# Daughterboard.net
KiCad netlist of a schematic drawn in EAGLE
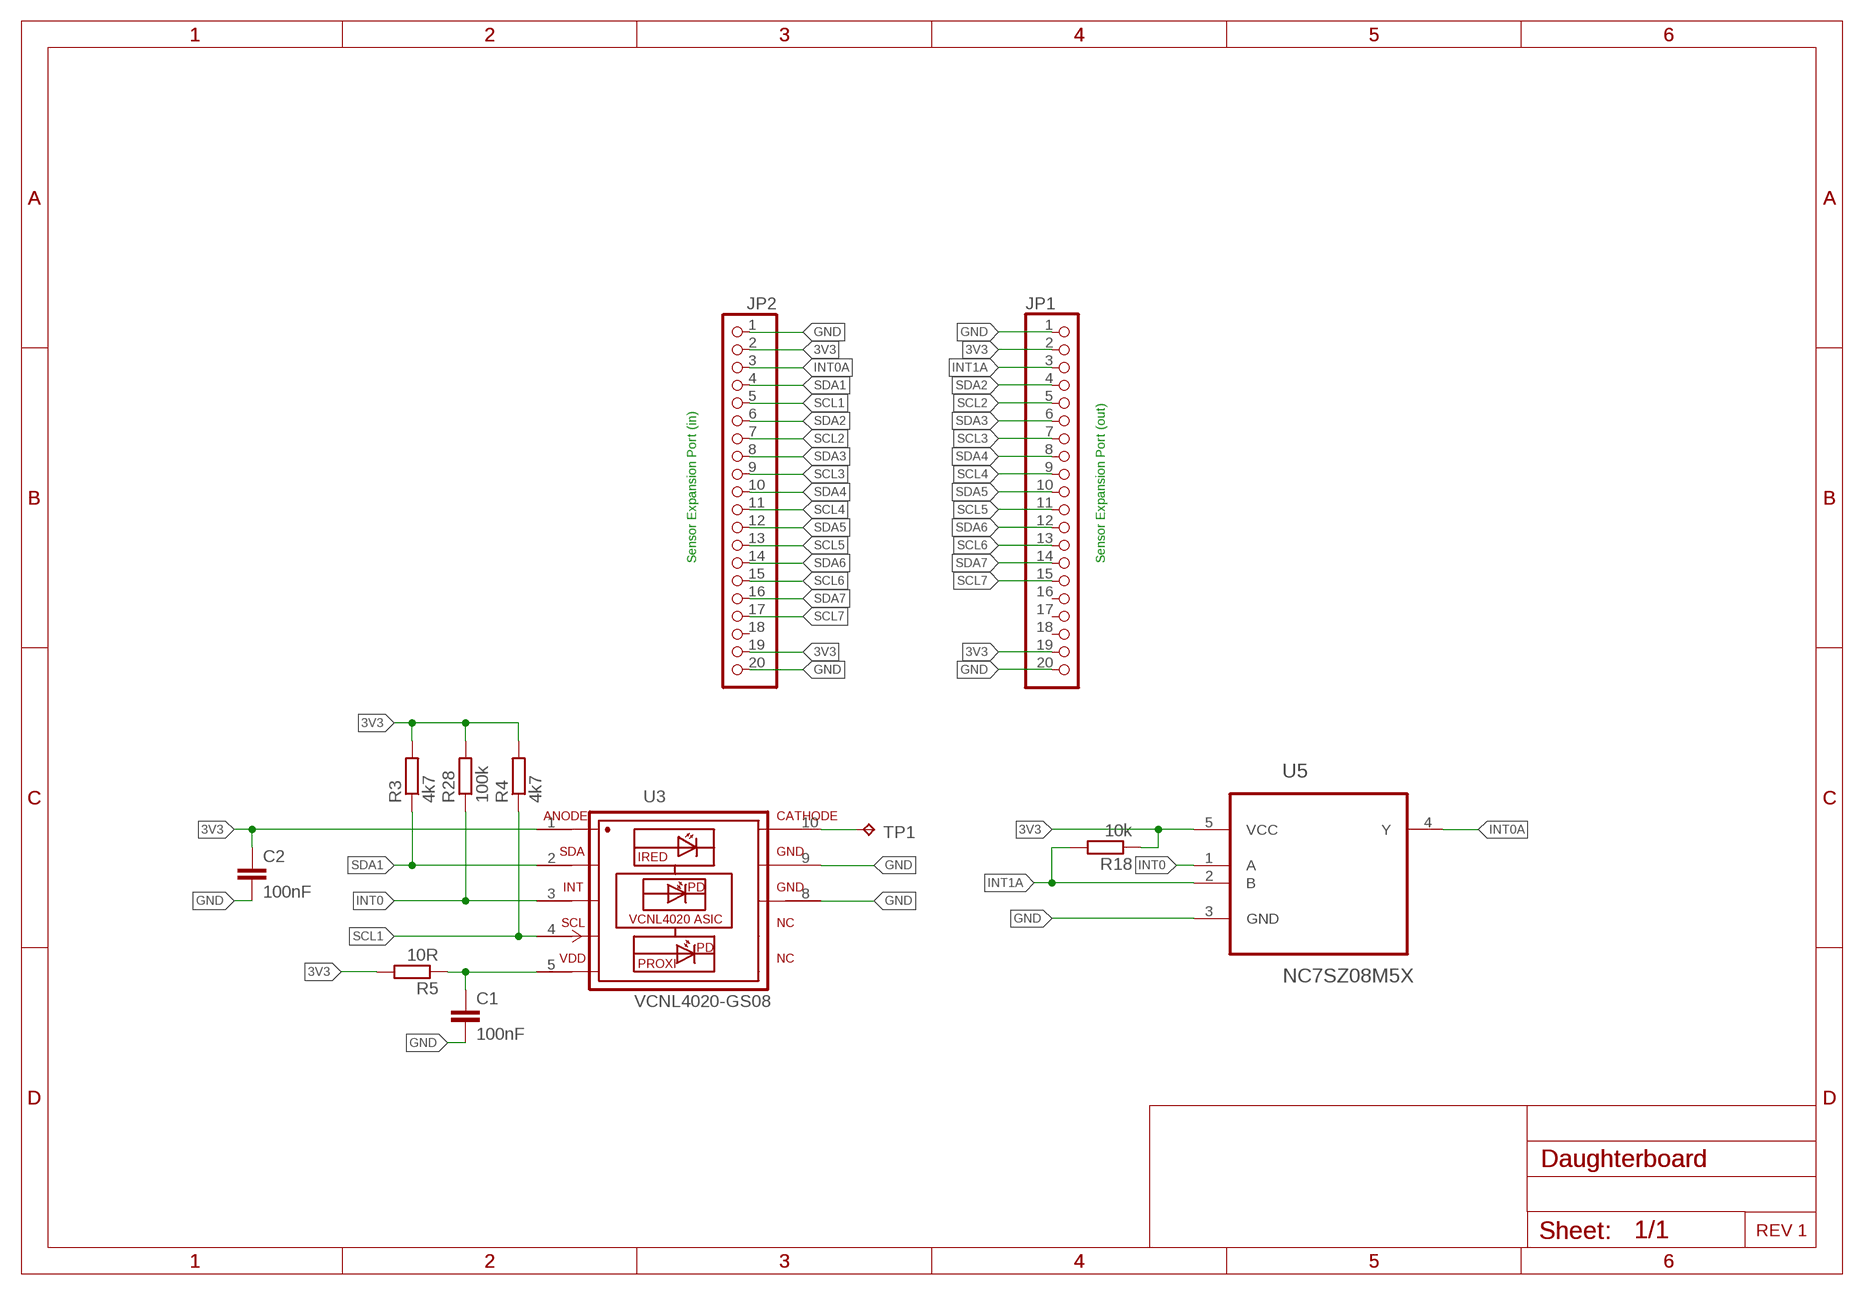
[diagram p0: schematic, sheet 1]

(export (version "E")
  (design (tool "Eeschema 10.0.6"))
  (components
    (comp (ref "C1")
      (value "100nF")
      (footprint "eagle-import:C0603")
      (libsource (lib "eagle-import") (part "C-EUC0603"))
    )
    (comp (ref "C2")
      (value "100nF")
      (footprint "eagle-import:C0603")
      (libsource (lib "eagle-import") (part "C-EUC0603"))
    )
    (comp (ref "JP1")
      (value "PINHD-1X20/90")
      (footprint "eagle-import:1X20_90")
      (libsource (lib "eagle-import") (part "PINHD-1X20/90"))
    )
    (comp (ref "JP2")
      (value "PINHD-1X20/90")
      (footprint "eagle-import:1X20_90")
      (libsource (lib "eagle-import") (part "PINHD-1X20/90"))
    )
    (comp (ref "R3")
      (value "4k7")
      (footprint "eagle-import:R0603")
      (libsource (lib "eagle-import") (part "R-EU_R0603"))
    )
    (comp (ref "R4")
      (value "4k7")
      (footprint "eagle-import:R0603")
      (libsource (lib "eagle-import") (part "R-EU_R0603"))
    )
    (comp (ref "R5")
      (value "10R")
      (footprint "eagle-import:R0603")
      (libsource (lib "eagle-import") (part "R-EU_R0603"))
    )
    (comp (ref "R18")
      (value "10k")
      (footprint "eagle-import:R0603")
      (libsource (lib "eagle-import") (part "R-EU_R0603"))
    )
    (comp (ref "R28")
      (value "100k")
      (footprint "eagle-import:R0603")
      (libsource (lib "eagle-import") (part "R-EU_R0603"))
    )
    (comp (ref "TP1")
      (value "TPB1,27")
      (footprint "eagle-import:B1,27")
      (libsource (lib "eagle-import") (part "TPB1,27"))
    )
    (comp (ref "U3")
      (value "VCNL4020-GS08")
      (footprint "eagle-import:PHODET_VCNL4020")
      (fields (field (name "MF") "Vishay Semiconductor"))
      (libsource (lib "eagle-import") (part "VCNL4020-GS08"))
    )
    (comp (ref "U5")
      (value "NC7SZ08M5X")
      (footprint "eagle-import:SOT95P280X145-5N")
      (fields
        (field (name "DIGI-KEY_PART_NUMBER") "NC7SZ08M5XCT-ND")
        (field (name "MF") "ON Semiconductor")
        (field (name "DIGI-KEY_PART_NUMBER_1") "NC7SZ08M5XCT-ND")
        (field (name "DIGI-KEY_PURCHASE_URL") "https://www.digikey.com/product-detail/en/on-semiconductor/NC7SZ08M5X/NC7SZ08M5XCT-ND/673390?utm_source=snapeda&utm_medium=aggregator&utm_campaign=symbol")
        (field (name "MP") "NC7SZ08M5X")
        (field (name "PACKAGE") "SOT-23 Texas Instruments")
      )
      (libsource (lib "eagle-import") (part "NC7SZ08M5X"))
    )
  )
  (nets
    (net (code "1") (name "3V3") (class "Default")
      (node (ref "C2") (pin "1") (pinfunction "1_1") (pintype "passive"))
      (node (ref "JP1") (pin "19") (pinfunction "19_19") (pintype "passive"))
      (node (ref "JP1") (pin "2") (pinfunction "2_2") (pintype "passive"))
      (node (ref "JP2") (pin "19") (pinfunction "19_19") (pintype "passive"))
      (node (ref "JP2") (pin "2") (pinfunction "2_2") (pintype "passive"))
      (node (ref "R18") (pin "1") (pinfunction "1_1") (pintype "passive"))
      (node (ref "R28") (pin "2") (pinfunction "2_2") (pintype "passive"))
      (node (ref "R3") (pin "2") (pinfunction "2_2") (pintype "passive"))
      (node (ref "R4") (pin "2") (pinfunction "2_2") (pintype "passive"))
      (node (ref "R5") (pin "2") (pinfunction "2_2") (pintype "passive"))
      (node (ref "U3") (pin "1") (pinfunction "IR-ANODE_1") (pintype "passive"))
      (node (ref "U5") (pin "5") (pinfunction "VCC_5") (pintype "power_in"))
    )
    (net (code "2") (name "GND") (class "Default")
      (node (ref "C1") (pin "2") (pinfunction "2_2") (pintype "passive"))
      (node (ref "C2") (pin "2") (pinfunction "2_2") (pintype "passive"))
      (node (ref "JP1") (pin "1") (pinfunction "1_1") (pintype "passive"))
      (node (ref "JP1") (pin "20") (pinfunction "20_20") (pintype "passive"))
      (node (ref "JP2") (pin "1") (pinfunction "1_1") (pintype "passive"))
      (node (ref "JP2") (pin "20") (pinfunction "20_20") (pintype "passive"))
      (node (ref "U3") (pin "8") (pinfunction "GND2_8") (pintype "power_in"))
      (node (ref "U3") (pin "9") (pinfunction "GND_9") (pintype "power_in"))
      (node (ref "U5") (pin "3") (pinfunction "GND_3") (pintype "passive"))
    )
    (net (code "3") (name "INT0") (class "Default")
      (node (ref "R28") (pin "1") (pinfunction "1_1") (pintype "passive"))
      (node (ref "U3") (pin "3") (pinfunction "INT_3") (pintype "output"))
      (node (ref "U5") (pin "1") (pinfunction "A_1") (pintype "input"))
    )
    (net (code "4") (name "INT0A") (class "Default")
      (node (ref "JP2") (pin "3") (pinfunction "3_3") (pintype "passive"))
      (node (ref "U5") (pin "4") (pinfunction "Y_4") (pintype "output"))
    )
    (net (code "5") (name "INT1A") (class "Default")
      (node (ref "JP1") (pin "3") (pinfunction "3_3") (pintype "passive"))
      (node (ref "R18") (pin "2") (pinfunction "2_2") (pintype "passive"))
      (node (ref "U5") (pin "2") (pinfunction "B_2") (pintype "input"))
    )
    (net (code "6") (name "Net-(U3-IR-CATHODE)") (class "Default")
      (node (ref "TP1") (pin "TP") (pinfunction "TP_TP") (pintype "input"))
      (node (ref "U3") (pin "10") (pinfunction "IR-CATHODE_10") (pintype "passive"))
    )
    (net (code "7") (name "Net-(U3-VDD)") (class "Default")
      (node (ref "C1") (pin "1") (pinfunction "1_1") (pintype "passive"))
      (node (ref "R5") (pin "1") (pinfunction "1_1") (pintype "passive"))
      (node (ref "U3") (pin "5") (pinfunction "VDD_5") (pintype "power_in"))
    )
    (net (code "8") (name "SCL1") (class "Default")
      (node (ref "JP2") (pin "5") (pinfunction "5_5") (pintype "passive"))
      (node (ref "R4") (pin "1") (pinfunction "1_1") (pintype "passive"))
      (node (ref "U3") (pin "4") (pinfunction "SCL_4") (pintype "input"))
    )
    (net (code "9") (name "SCL2") (class "Default")
      (node (ref "JP1") (pin "5") (pinfunction "5_5") (pintype "passive"))
      (node (ref "JP2") (pin "7") (pinfunction "7_7") (pintype "passive"))
    )
    (net (code "10") (name "SCL3") (class "Default")
      (node (ref "JP1") (pin "7") (pinfunction "7_7") (pintype "passive"))
      (node (ref "JP2") (pin "9") (pinfunction "9_9") (pintype "passive"))
    )
    (net (code "11") (name "SCL4") (class "Default")
      (node (ref "JP1") (pin "9") (pinfunction "9_9") (pintype "passive"))
      (node (ref "JP2") (pin "11") (pinfunction "11_11") (pintype "passive"))
    )
    (net (code "12") (name "SCL5") (class "Default")
      (node (ref "JP1") (pin "11") (pinfunction "11_11") (pintype "passive"))
      (node (ref "JP2") (pin "13") (pinfunction "13_13") (pintype "passive"))
    )
    (net (code "13") (name "SCL6") (class "Default")
      (node (ref "JP1") (pin "13") (pinfunction "13_13") (pintype "passive"))
      (node (ref "JP2") (pin "15") (pinfunction "15_15") (pintype "passive"))
    )
    (net (code "14") (name "SCL7") (class "Default")
      (node (ref "JP1") (pin "15") (pinfunction "15_15") (pintype "passive"))
      (node (ref "JP2") (pin "17") (pinfunction "17_17") (pintype "passive"))
    )
    (net (code "15") (name "SDA1") (class "Default")
      (node (ref "JP2") (pin "4") (pinfunction "4_4") (pintype "passive"))
      (node (ref "R3") (pin "1") (pinfunction "1_1") (pintype "passive"))
      (node (ref "U3") (pin "2") (pinfunction "SDA_2") (pintype "bidirectional"))
    )
    (net (code "16") (name "SDA2") (class "Default")
      (node (ref "JP1") (pin "4") (pinfunction "4_4") (pintype "passive"))
      (node (ref "JP2") (pin "6") (pinfunction "6_6") (pintype "passive"))
    )
    (net (code "17") (name "SDA3") (class "Default")
      (node (ref "JP1") (pin "6") (pinfunction "6_6") (pintype "passive"))
      (node (ref "JP2") (pin "8") (pinfunction "8_8") (pintype "passive"))
    )
    (net (code "18") (name "SDA4") (class "Default")
      (node (ref "JP1") (pin "8") (pinfunction "8_8") (pintype "passive"))
      (node (ref "JP2") (pin "10") (pinfunction "10_10") (pintype "passive"))
    )
    (net (code "19") (name "SDA5") (class "Default")
      (node (ref "JP1") (pin "10") (pinfunction "10_10") (pintype "passive"))
      (node (ref "JP2") (pin "12") (pinfunction "12_12") (pintype "passive"))
    )
    (net (code "20") (name "SDA6") (class "Default")
      (node (ref "JP1") (pin "12") (pinfunction "12_12") (pintype "passive"))
      (node (ref "JP2") (pin "14") (pinfunction "14_14") (pintype "passive"))
    )
    (net (code "21") (name "SDA7") (class "Default")
      (node (ref "JP1") (pin "14") (pinfunction "14_14") (pintype "passive"))
      (node (ref "JP2") (pin "16") (pinfunction "16_16") (pintype "passive"))
    )
    (net (code "22") (name "unconnected-(JP1-Pad16)") (class "Default")
      (node (ref "JP1") (pin "16") (pinfunction "16_16") (pintype "passive"))
    )
    (net (code "23") (name "unconnected-(JP1-Pad17)") (class "Default")
      (node (ref "JP1") (pin "17") (pinfunction "17_17") (pintype "passive"))
    )
    (net (code "24") (name "unconnected-(JP1-Pad18)") (class "Default")
      (node (ref "JP1") (pin "18") (pinfunction "18_18") (pintype "passive"))
    )
    (net (code "25") (name "unconnected-(JP2-Pad18)") (class "Default")
      (node (ref "JP2") (pin "18") (pinfunction "18_18") (pintype "passive"))
    )
  )
)
